# OMSI_TABLE_R12_v3.net
KiCad netlist of a schematic drawn in EAGLE
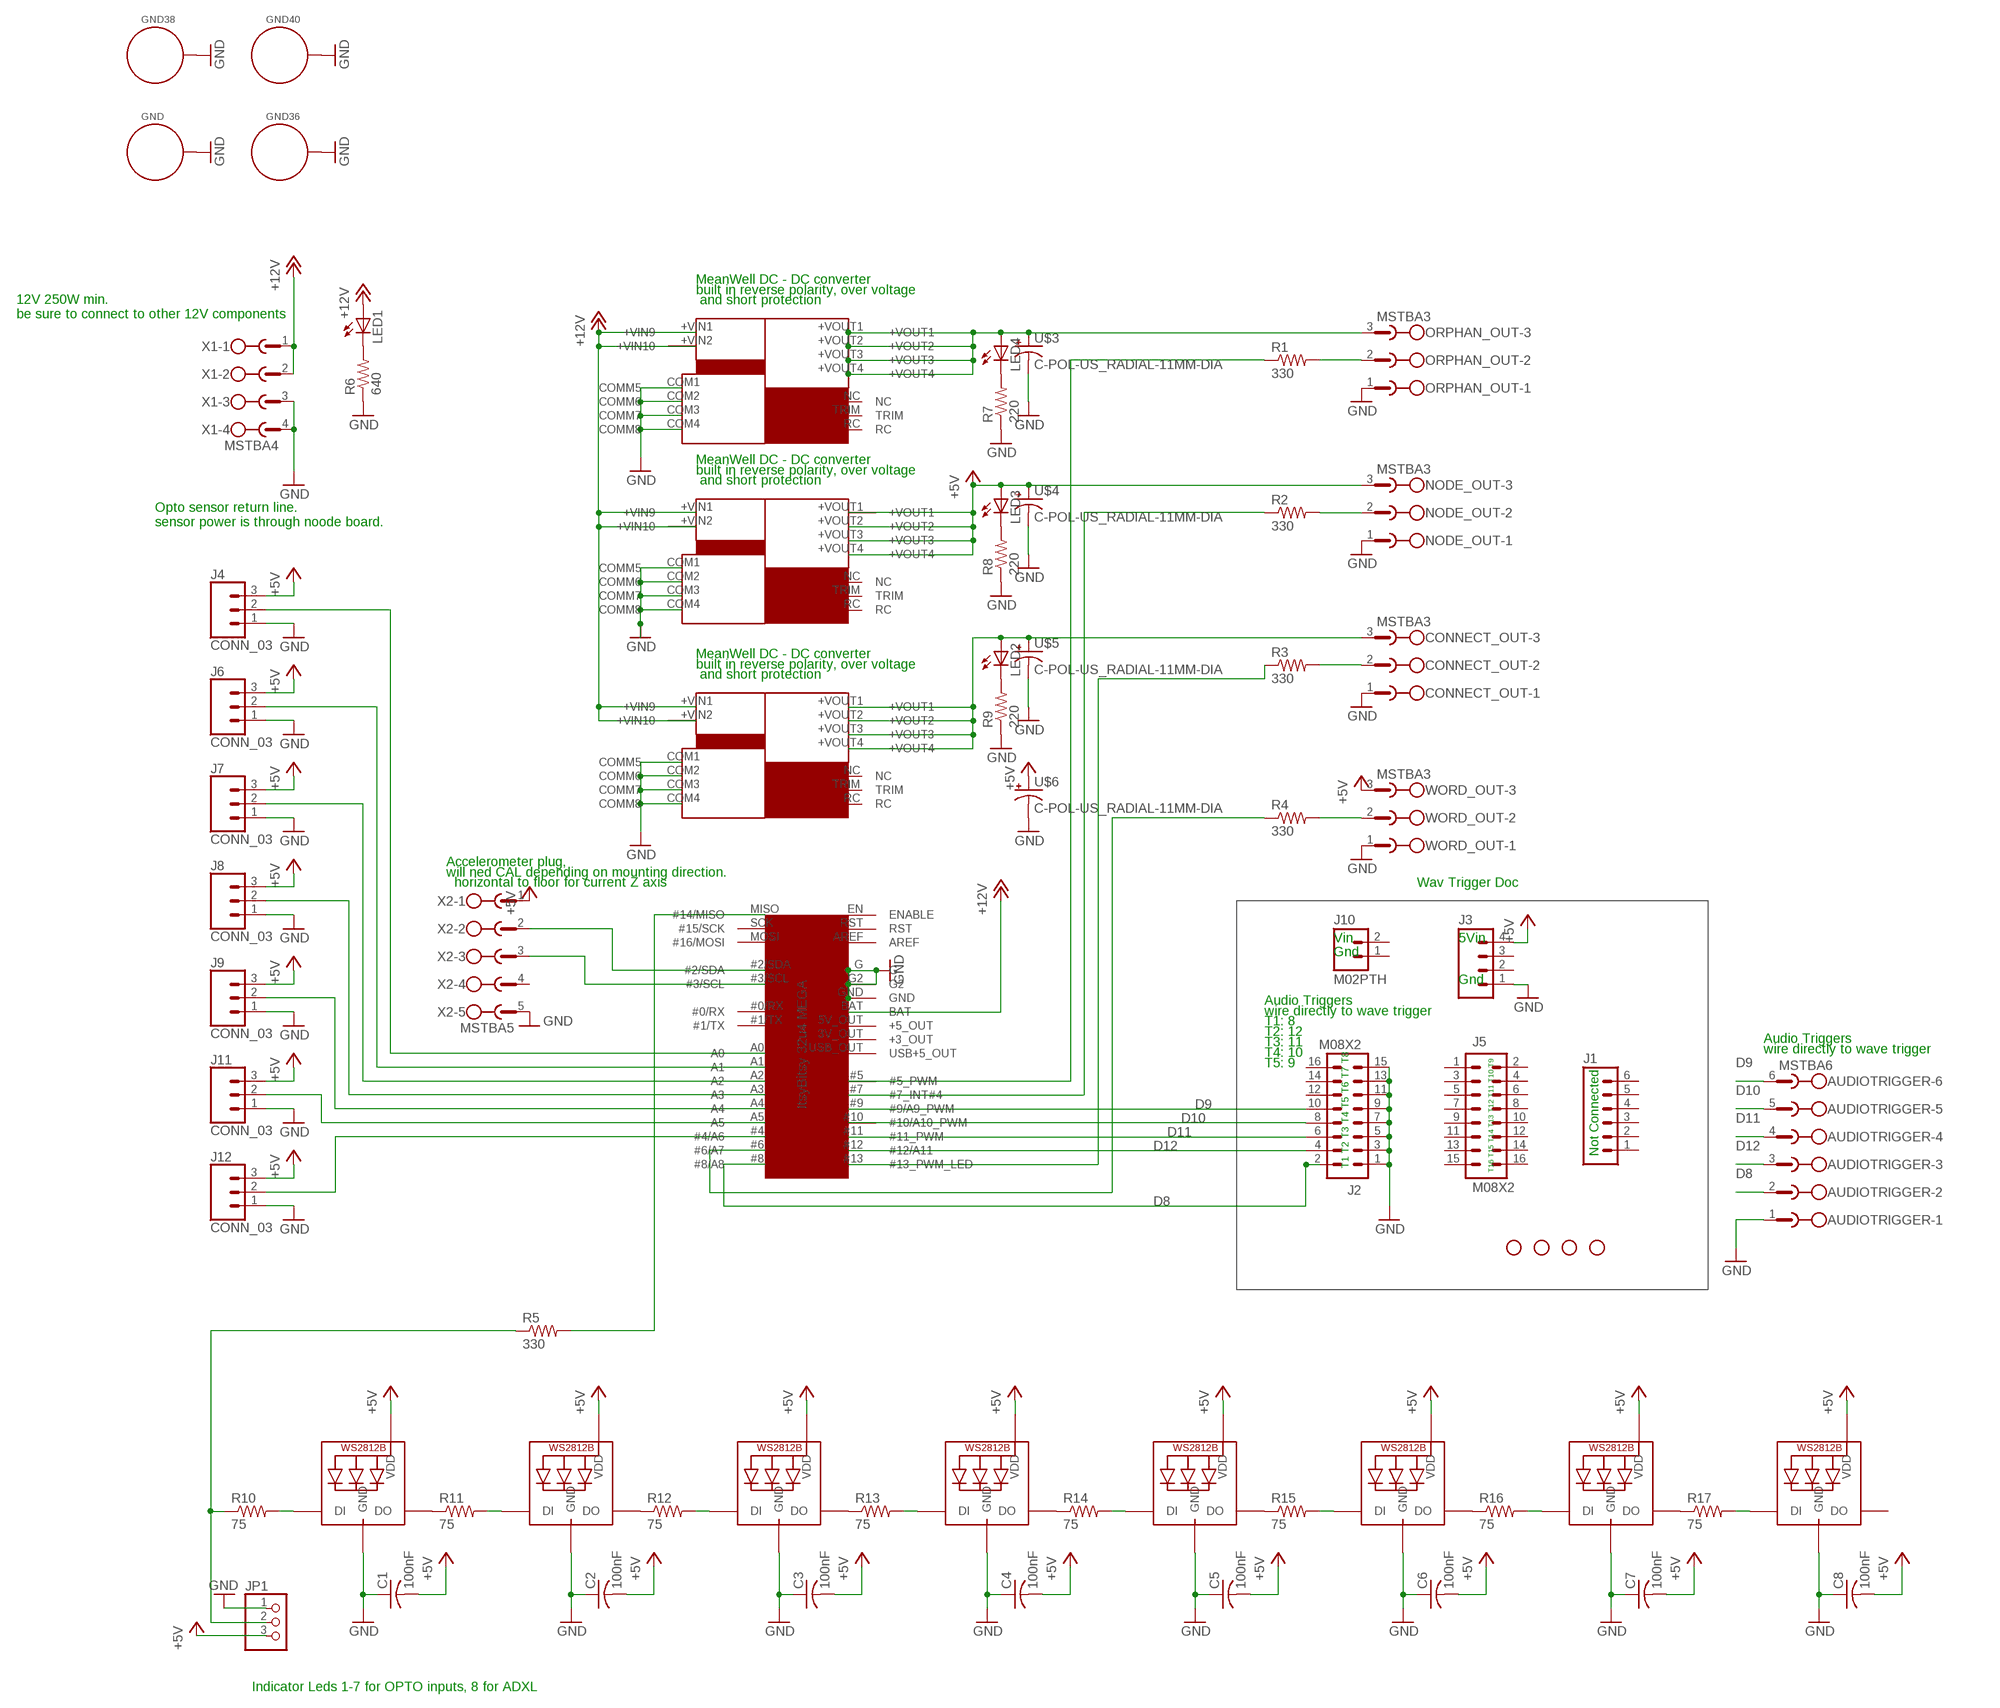
[diagram p0: schematic, sheet 1]

(export (version "E")
  (design (tool "Eeschema 10.0.6"))
  (components
    (comp (ref "AUDIOTRIGGER")
      (value "MSTBA6")
      (footprint "eagle-import:MSTBA6")
      (fields (field (name "MF") "FARNELL") (field (name "MPN") "1757284"))
      (libsource (lib "eagle-import") (part "MSTBA6"))
    )
    (comp (ref "C1")
      (value "100nF")
      (footprint "eagle-import:C0805")
      (libsource (lib "eagle-import") (part "C-USC0805"))
    )
    (comp (ref "C2")
      (value "100nF")
      (footprint "eagle-import:C0805")
      (libsource (lib "eagle-import") (part "C-USC0805"))
    )
    (comp (ref "C3")
      (value "100nF")
      (footprint "eagle-import:C0805")
      (libsource (lib "eagle-import") (part "C-USC0805"))
    )
    (comp (ref "C4")
      (value "100nF")
      (footprint "eagle-import:C0805")
      (libsource (lib "eagle-import") (part "C-USC0805"))
    )
    (comp (ref "C5")
      (value "100nF")
      (footprint "eagle-import:C0805")
      (libsource (lib "eagle-import") (part "C-USC0805"))
    )
    (comp (ref "C6")
      (value "100nF")
      (footprint "eagle-import:C0805")
      (libsource (lib "eagle-import") (part "C-USC0805"))
    )
    (comp (ref "C7")
      (value "100nF")
      (footprint "eagle-import:C0805")
      (libsource (lib "eagle-import") (part "C-USC0805"))
    )
    (comp (ref "C8")
      (value "100nF")
      (footprint "eagle-import:C0805")
      (libsource (lib "eagle-import") (part "C-USC0805"))
    )
    (comp (ref "CONNECT_OUT")
      (value "MSTBA3")
      (footprint "eagle-import:MSTBA3")
      (fields (field (name "MF") "FARNELL") (field (name "MPN") "1757255"))
      (libsource (lib "eagle-import") (part "MSTBA3"))
    )
    (comp (ref "GND")
      (value "STANDOFF_ELECTRICAL5-32")
      (footprint "eagle-import:STANDOFF_ELECTRICAL_5_32")
      (libsource (lib "eagle-import") (part "STANDOFF_ELECTRICAL5-32"))
    )
    (comp (ref "GND36")
      (value "STANDOFF_ELECTRICAL5-32")
      (footprint "eagle-import:STANDOFF_ELECTRICAL_5_32")
      (libsource (lib "eagle-import") (part "STANDOFF_ELECTRICAL5-32"))
    )
    (comp (ref "GND38")
      (value "STANDOFF_ELECTRICAL5-32")
      (footprint "eagle-import:STANDOFF_ELECTRICAL_5_32")
      (libsource (lib "eagle-import") (part "STANDOFF_ELECTRICAL5-32"))
    )
    (comp (ref "GND40")
      (value "STANDOFF_ELECTRICAL5-32")
      (footprint "eagle-import:STANDOFF_ELECTRICAL_5_32")
      (libsource (lib "eagle-import") (part "STANDOFF_ELECTRICAL5-32"))
    )
    (comp (ref "J1")
      (value "M06SIP")
      (footprint "eagle-import:1X06")
      (libsource (lib "eagle-import") (part "M06SIP"))
    )
    (comp (ref "J2")
      (value "M08X2")
      (footprint "eagle-import:2X8")
      (libsource (lib "eagle-import") (part "M08X2"))
    )
    (comp (ref "J3")
      (value "M04PTH")
      (footprint "eagle-import:1X04")
      (libsource (lib "eagle-import") (part "M04PTH"))
    )
    (comp (ref "J4")
      (value "CONN_03")
      (footprint "eagle-import:1X03_3.5MM_RA")
      (libsource (lib "eagle-import") (part "CONN_03"))
    )
    (comp (ref "J5")
      (value "M08X2")
      (footprint "eagle-import:2X8")
      (libsource (lib "eagle-import") (part "M08X2"))
    )
    (comp (ref "J6")
      (value "CONN_03")
      (footprint "eagle-import:1X03_3.5MM_RA")
      (libsource (lib "eagle-import") (part "CONN_03"))
    )
    (comp (ref "J7")
      (value "CONN_03")
      (footprint "eagle-import:1X03_3.5MM_RA")
      (libsource (lib "eagle-import") (part "CONN_03"))
    )
    (comp (ref "J8")
      (value "CONN_03")
      (footprint "eagle-import:1X03_3.5MM_RA")
      (libsource (lib "eagle-import") (part "CONN_03"))
    )
    (comp (ref "J9")
      (value "CONN_03")
      (footprint "eagle-import:1X03_3.5MM_RA")
      (libsource (lib "eagle-import") (part "CONN_03"))
    )
    (comp (ref "J10")
      (value "M02PTH")
      (footprint "eagle-import:1X02")
      (libsource (lib "eagle-import") (part "M02PTH"))
    )
    (comp (ref "J11")
      (value "CONN_03")
      (footprint "eagle-import:1X03_3.5MM_RA")
      (libsource (lib "eagle-import") (part "CONN_03"))
    )
    (comp (ref "J12")
      (value "CONN_03")
      (footprint "eagle-import:1X03_3.5MM_RA")
      (libsource (lib "eagle-import") (part "CONN_03"))
    )
    (comp (ref "JP1")
      (value "PINHD-1X3")
      (footprint "eagle-import:1X03")
      (libsource (lib "eagle-import") (part "PINHD-1X3"))
    )
    (comp (ref "LED1")
      (value "LEDCHIPLED_1206")
      (footprint "eagle-import:CHIPLED_1206")
      (libsource (lib "eagle-import") (part "LEDCHIPLED_1206"))
    )
    (comp (ref "LED2")
      (value "LEDCHIPLED_1206")
      (footprint "eagle-import:CHIPLED_1206")
      (libsource (lib "eagle-import") (part "LEDCHIPLED_1206"))
    )
    (comp (ref "LED3")
      (value "LEDCHIPLED_1206")
      (footprint "eagle-import:CHIPLED_1206")
      (libsource (lib "eagle-import") (part "LEDCHIPLED_1206"))
    )
    (comp (ref "LED4")
      (value "LEDCHIPLED_1206")
      (footprint "eagle-import:CHIPLED_1206")
      (libsource (lib "eagle-import") (part "LEDCHIPLED_1206"))
    )
    (comp (ref "LED5")
      (value "WS2812B")
      (footprint "eagle-import:WS2812D-F5")
      (libsource (lib "eagle-import") (part "WS2812B"))
    )
    (comp (ref "LED6")
      (value "WS2812B")
      (footprint "eagle-import:WS2812D-F5")
      (libsource (lib "eagle-import") (part "WS2812B"))
    )
    (comp (ref "LED7")
      (value "WS2812B")
      (footprint "eagle-import:WS2812D-F5")
      (libsource (lib "eagle-import") (part "WS2812B"))
    )
    (comp (ref "LED8")
      (value "WS2812B")
      (footprint "eagle-import:WS2812D-F5")
      (libsource (lib "eagle-import") (part "WS2812B"))
    )
    (comp (ref "LED9")
      (value "WS2812B")
      (footprint "eagle-import:WS2812D-F5")
      (libsource (lib "eagle-import") (part "WS2812B"))
    )
    (comp (ref "LED10")
      (value "WS2812B")
      (footprint "eagle-import:WS2812D-F5")
      (libsource (lib "eagle-import") (part "WS2812B"))
    )
    (comp (ref "LED11")
      (value "WS2812B")
      (footprint "eagle-import:WS2812D-F5")
      (libsource (lib "eagle-import") (part "WS2812B"))
    )
    (comp (ref "LED12")
      (value "WS2812B")
      (footprint "eagle-import:WS2812D-F5")
      (libsource (lib "eagle-import") (part "WS2812B"))
    )
    (comp (ref "MEANWELL_NID100_1")
      (value "MEANWELL_NID100")
      (footprint "eagle-import:MEANWELL_NID100")
      (libsource (lib "eagle-import") (part "MEANWELL_NID100"))
    )
    (comp (ref "MEANWELL_NID100_2")
      (value "MEANWELL_NID100")
      (footprint "eagle-import:MEANWELL_NID100")
      (libsource (lib "eagle-import") (part "MEANWELL_NID100"))
    )
    (comp (ref "MEANWELL_NID100_3")
      (value "MEANWELL_NID100")
      (footprint "eagle-import:MEANWELL_NID100")
      (libsource (lib "eagle-import") (part "MEANWELL_NID100"))
    )
    (comp (ref "NODE_OUT")
      (value "MSTBA3")
      (footprint "eagle-import:MSTBA3")
      (fields (field (name "MF") "FARNELL") (field (name "MPN") "1757255"))
      (libsource (lib "eagle-import") (part "MSTBA3"))
    )
    (comp (ref "ORPHAN_OUT")
      (value "MSTBA3")
      (footprint "eagle-import:MSTBA3")
      (fields (field (name "MF") "FARNELL") (field (name "MPN") "1757255"))
      (libsource (lib "eagle-import") (part "MSTBA3"))
    )
    (comp (ref "R1")
      (value "330")
      (footprint "eagle-import:RESAD1176W63L850D250B")
      (libsource (lib "eagle-import") (part "R-USAXIAL-11.7MM-PITCH_"))
    )
    (comp (ref "R2")
      (value "330")
      (footprint "eagle-import:RESAD1176W63L850D250B")
      (libsource (lib "eagle-import") (part "R-USAXIAL-11.7MM-PITCH_"))
    )
    (comp (ref "R3")
      (value "330")
      (footprint "eagle-import:RESAD1176W63L850D250B")
      (libsource (lib "eagle-import") (part "R-USAXIAL-11.7MM-PITCH_"))
    )
    (comp (ref "R4")
      (value "330")
      (footprint "eagle-import:RESAD1176W63L850D250B")
      (libsource (lib "eagle-import") (part "R-USAXIAL-11.7MM-PITCH_"))
    )
    (comp (ref "R5")
      (value "330")
      (footprint "eagle-import:RESAD1176W63L850D250B")
      (libsource (lib "eagle-import") (part "R-USAXIAL-11.7MM-PITCH_"))
    )
    (comp (ref "R6")
      (value "640")
      (footprint "eagle-import:R0805")
      (libsource (lib "eagle-import") (part "adafruit_420_R-US_R0805"))
    )
    (comp (ref "R7")
      (value "220")
      (footprint "eagle-import:R0805")
      (libsource (lib "eagle-import") (part "R-US_R0805"))
    )
    (comp (ref "R8")
      (value "220")
      (footprint "eagle-import:R0805")
      (libsource (lib "eagle-import") (part "R-US_R0805"))
    )
    (comp (ref "R9")
      (value "220")
      (footprint "eagle-import:R0805")
      (libsource (lib "eagle-import") (part "R-US_R0805"))
    )
    (comp (ref "R10")
      (value "75")
      (footprint "eagle-import:R0805")
      (libsource (lib "eagle-import") (part "adafruit_420_R-US_R0805"))
    )
    (comp (ref "R11")
      (value "75")
      (footprint "eagle-import:R0805")
      (libsource (lib "eagle-import") (part "adafruit_420_R-US_R0805"))
    )
    (comp (ref "R12")
      (value "75")
      (footprint "eagle-import:R0805")
      (libsource (lib "eagle-import") (part "adafruit_420_R-US_R0805"))
    )
    (comp (ref "R13")
      (value "75")
      (footprint "eagle-import:R0805")
      (libsource (lib "eagle-import") (part "adafruit_420_R-US_R0805"))
    )
    (comp (ref "R14")
      (value "75")
      (footprint "eagle-import:R0805")
      (libsource (lib "eagle-import") (part "adafruit_420_R-US_R0805"))
    )
    (comp (ref "R15")
      (value "75")
      (footprint "eagle-import:R0805")
      (libsource (lib "eagle-import") (part "adafruit_420_R-US_R0805"))
    )
    (comp (ref "R16")
      (value "75")
      (footprint "eagle-import:R0805")
      (libsource (lib "eagle-import") (part "adafruit_420_R-US_R0805"))
    )
    (comp (ref "R17")
      (value "75")
      (footprint "eagle-import:R0805")
      (libsource (lib "eagle-import") (part "adafruit_420_R-US_R0805"))
    )
    (comp (ref "STANDOFF5")
      (value "STAND-OFF")
      (footprint "eagle-import:STAND-OFF")
      (libsource (lib "eagle-import") (part "STAND-OFF"))
    )
    (comp (ref "STANDOFF6")
      (value "STAND-OFF")
      (footprint "eagle-import:STAND-OFF")
      (libsource (lib "eagle-import") (part "STAND-OFF"))
    )
    (comp (ref "STANDOFF7")
      (value "STAND-OFF")
      (footprint "eagle-import:STAND-OFF")
      (libsource (lib "eagle-import") (part "STAND-OFF"))
    )
    (comp (ref "STANDOFF8")
      (value "STAND-OFF")
      (footprint "eagle-import:STAND-OFF")
      (libsource (lib "eagle-import") (part "STAND-OFF"))
    )
    (comp (ref "U$1")
      (value "ITSYBITSY_32U4")
      (footprint "eagle-import:ITSYBITSY_32U4")
      (libsource (lib "eagle-import") (part "ITSYBITSY_32U4"))
    )
    (comp (ref "U$3")
      (value "C-POL-US_RADIAL-11MM-DIA")
      (footprint "eagle-import:CAPPRD508W65D1000H1100B")
      (libsource (lib "eagle-import") (part "C-POL-USRADIAL-11MM-DIA_"))
    )
    (comp (ref "U$4")
      (value "C-POL-US_RADIAL-11MM-DIA")
      (footprint "eagle-import:CAPPRD508W65D1000H1100B")
      (libsource (lib "eagle-import") (part "C-POL-USRADIAL-11MM-DIA_"))
    )
    (comp (ref "U$5")
      (value "C-POL-US_RADIAL-11MM-DIA")
      (footprint "eagle-import:CAPPRD508W65D1000H1100B")
      (libsource (lib "eagle-import") (part "C-POL-USRADIAL-11MM-DIA_"))
    )
    (comp (ref "U$6")
      (value "C-POL-US_RADIAL-11MM-DIA")
      (footprint "eagle-import:CAPPRD508W65D1000H1100B")
      (libsource (lib "eagle-import") (part "C-POL-USRADIAL-11MM-DIA_"))
    )
    (comp (ref "WORD_OUT")
      (value "MSTBA3")
      (footprint "eagle-import:MSTBA3")
      (fields (field (name "MF") "FARNELL") (field (name "MPN") "1757255"))
      (libsource (lib "eagle-import") (part "MSTBA3"))
    )
    (comp (ref "X1")
      (value "MSTBA4")
      (footprint "eagle-import:MSTBA4")
      (fields (field (name "MF") "FARNELL") (field (name "MPN") "1757268"))
      (libsource (lib "eagle-import") (part "MSTBA4"))
    )
    (comp (ref "X2")
      (value "MSTBA5")
      (footprint "eagle-import:MSTBA5")
      (fields (field (name "MPN") "1757271"))
      (libsource (lib "eagle-import") (part "MSTBA5"))
    )
  )
  (nets
    (net (code "1") (name "+5V") (class "Default")
      (node (ref "C1") (pin "2") (pinfunction "2_2") (pintype "passive"))
      (node (ref "C2") (pin "2") (pinfunction "2_2") (pintype "passive"))
      (node (ref "C3") (pin "2") (pinfunction "2_2") (pintype "passive"))
      (node (ref "C4") (pin "2") (pinfunction "2_2") (pintype "passive"))
      (node (ref "C5") (pin "2") (pinfunction "2_2") (pintype "passive"))
      (node (ref "C6") (pin "2") (pinfunction "2_2") (pintype "passive"))
      (node (ref "C7") (pin "2") (pinfunction "2_2") (pintype "passive"))
      (node (ref "C8") (pin "2") (pinfunction "2_2") (pintype "passive"))
      (node (ref "J11") (pin "3") (pinfunction "3_3") (pintype "passive"))
      (node (ref "J12") (pin "3") (pinfunction "3_3") (pintype "passive"))
      (node (ref "J3") (pin "4") (pinfunction "4_4") (pintype "passive"))
      (node (ref "J4") (pin "3") (pinfunction "3_3") (pintype "passive"))
      (node (ref "J6") (pin "3") (pinfunction "3_3") (pintype "passive"))
      (node (ref "J7") (pin "3") (pinfunction "3_3") (pintype "passive"))
      (node (ref "J8") (pin "3") (pinfunction "3_3") (pintype "passive"))
      (node (ref "J9") (pin "3") (pinfunction "3_3") (pintype "passive"))
      (node (ref "JP1") (pin "3") (pinfunction "3_3") (pintype "passive"))
      (node (ref "LED10") (pin "P$2") (pinfunction "VDD_P$2") (pintype "power_in"))
      (node (ref "LED11") (pin "P$2") (pinfunction "VDD_P$2") (pintype "power_in"))
      (node (ref "LED12") (pin "P$2") (pinfunction "VDD_P$2") (pintype "power_in"))
      (node (ref "LED3") (pin "A") (pinfunction "A_A") (pintype "passive"))
      (node (ref "LED5") (pin "P$2") (pinfunction "VDD_P$2") (pintype "power_in"))
      (node (ref "LED6") (pin "P$2") (pinfunction "VDD_P$2") (pintype "power_in"))
      (node (ref "LED7") (pin "P$2") (pinfunction "VDD_P$2") (pintype "power_in"))
      (node (ref "LED8") (pin "P$2") (pinfunction "VDD_P$2") (pintype "power_in"))
      (node (ref "LED9") (pin "P$2") (pinfunction "VDD_P$2") (pintype "power_in"))
      (node (ref "MEANWELL_NID100_3") (pin "+VOUT1") (pinfunction "+VOUT1_+VOUT1") (pintype "power_in"))
      (node (ref "MEANWELL_NID100_3") (pin "+VOUT2") (pinfunction "+VOUT2_+VOUT2") (pintype "power_in"))
      (node (ref "MEANWELL_NID100_3") (pin "+VOUT3") (pinfunction "+VOUT3_+VOUT3") (pintype "power_in"))
      (node (ref "MEANWELL_NID100_3") (pin "+VOUT4") (pinfunction "+VOUT4_+VOUT4") (pintype "power_in"))
      (node (ref "NODE_OUT") (pin "3") (pinfunction "1_3") (pintype "passive"))
      (node (ref "U$4") (pin "1") (pinfunction "+_1") (pintype "passive"))
      (node (ref "U$6") (pin "1") (pinfunction "+_1") (pintype "passive"))
      (node (ref "WORD_OUT") (pin "3") (pinfunction "1_3") (pintype "passive"))
      (node (ref "X2") (pin "1") (pinfunction "1_1") (pintype "passive"))
    )
    (net (code "2") (name "+12V") (class "Default")
      (node (ref "LED1") (pin "A") (pinfunction "A_A") (pintype "passive"))
      (node (ref "MEANWELL_NID100_1") (pin "+VIN1") (pinfunction "+VIN9_+VIN1") (pintype "power_in"))
      (node (ref "MEANWELL_NID100_1") (pin "+VIN2") (pinfunction "+VIN10_+VIN2") (pintype "power_in"))
      (node (ref "MEANWELL_NID100_2") (pin "+VIN1") (pinfunction "+VIN9_+VIN1") (pintype "power_in"))
      (node (ref "MEANWELL_NID100_2") (pin "+VIN2") (pinfunction "+VIN10_+VIN2") (pintype "power_in"))
      (node (ref "MEANWELL_NID100_3") (pin "+VIN1") (pinfunction "+VIN9_+VIN1") (pintype "power_in"))
      (node (ref "MEANWELL_NID100_3") (pin "+VIN2") (pinfunction "+VIN10_+VIN2") (pintype "power_in"))
      (node (ref "U$1") (pin "BAT") (pinfunction "BAT_BAT") (pintype "power_in"))
      (node (ref "X1") (pin "1") (pinfunction "1_1") (pintype "passive"))
      (node (ref "X1") (pin "2") (pinfunction "1_2") (pintype "passive"))
    )
    (net (code "3") (name "/+3_OUT") (class "Default")
      (node (ref "U$1") (pin "3V_OUT") (pinfunction "+3_OUT_3V_OUT") (pintype "power_in"))
    )
    (net (code "4") (name "/+5_OUT") (class "Default")
      (node (ref "U$1") (pin "5V_OUT") (pinfunction "+5_OUT_5V_OUT") (pintype "power_in"))
    )
    (net (code "5") (name "/AREF") (class "Default")
      (node (ref "U$1") (pin "AREF") (pinfunction "AREF_AREF") (pintype "power_in"))
    )
    (net (code "6") (name "/D8") (class "Default")
      (node (ref "AUDIOTRIGGER") (pin "2") (pinfunction "1_2") (pintype "passive"))
      (node (ref "J2") (pin "2") (pinfunction "2_2") (pintype "passive"))
      (node (ref "U$1") (pin "#8") (pinfunction "#8/A8_#8") (pintype "bidirectional"))
    )
    (net (code "7") (name "/D9") (class "Default")
      (node (ref "AUDIOTRIGGER") (pin "6") (pinfunction "1_6") (pintype "passive"))
      (node (ref "J2") (pin "10") (pinfunction "10_10") (pintype "passive"))
      (node (ref "U$1") (pin "#9") (pinfunction "#9/A9_PWM_#9") (pintype "bidirectional"))
    )
    (net (code "8") (name "/D10") (class "Default")
      (node (ref "AUDIOTRIGGER") (pin "5") (pinfunction "1_5") (pintype "passive"))
      (node (ref "J2") (pin "8") (pinfunction "8_8") (pintype "passive"))
      (node (ref "U$1") (pin "#10") (pinfunction "#10/A10_PWM_#10") (pintype "bidirectional"))
    )
    (net (code "9") (name "/D11") (class "Default")
      (node (ref "AUDIOTRIGGER") (pin "4") (pinfunction "1_4") (pintype "passive"))
      (node (ref "J2") (pin "6") (pinfunction "6_6") (pintype "passive"))
      (node (ref "U$1") (pin "#11") (pinfunction "#11_PWM_#11") (pintype "bidirectional"))
    )
    (net (code "10") (name "/D12") (class "Default")
      (node (ref "AUDIOTRIGGER") (pin "3") (pinfunction "1_3") (pintype "passive"))
      (node (ref "J2") (pin "4") (pinfunction "4_4") (pintype "passive"))
      (node (ref "U$1") (pin "#12") (pinfunction "#12/A11_#12") (pintype "bidirectional"))
    )
    (net (code "11") (name "/RST") (class "Default")
      (node (ref "U$1") (pin "RST") (pinfunction "RST_RST") (pintype "power_in"))
    )
    (net (code "12") (name "/USB+5_OUT") (class "Default")
      (node (ref "U$1") (pin "USB_OUT") (pinfunction "USB+5_OUT_USB_OUT") (pintype "power_in"))
    )
    (net (code "13") (name "GND") (class "Default")
      (node (ref "AUDIOTRIGGER") (pin "1") (pinfunction "1_1") (pintype "passive"))
      (node (ref "C1") (pin "1") (pinfunction "1_1") (pintype "passive"))
      (node (ref "C2") (pin "1") (pinfunction "1_1") (pintype "passive"))
      (node (ref "C3") (pin "1") (pinfunction "1_1") (pintype "passive"))
      (node (ref "C4") (pin "1") (pinfunction "1_1") (pintype "passive"))
      (node (ref "C5") (pin "1") (pinfunction "1_1") (pintype "passive"))
      (node (ref "C6") (pin "1") (pinfunction "1_1") (pintype "passive"))
      (node (ref "C7") (pin "1") (pinfunction "1_1") (pintype "passive"))
      (node (ref "C8") (pin "1") (pinfunction "1_1") (pintype "passive"))
      (node (ref "CONNECT_OUT") (pin "1") (pinfunction "1_1") (pintype "passive"))
      (node (ref "GND") (pin "P1") (pinfunction "P$1_P1") (pintype "bidirectional"))
      (node (ref "GND36") (pin "P1") (pinfunction "P$1_P1") (pintype "bidirectional"))
      (node (ref "GND38") (pin "P1") (pinfunction "P$1_P1") (pintype "bidirectional"))
      (node (ref "GND40") (pin "P1") (pinfunction "P$1_P1") (pintype "bidirectional"))
      (node (ref "J11") (pin "1") (pinfunction "1_1") (pintype "passive"))
      (node (ref "J12") (pin "1") (pinfunction "1_1") (pintype "passive"))
      (node (ref "J2") (pin "1") (pinfunction "1_1") (pintype "passive"))
      (node (ref "J2") (pin "11") (pinfunction "11_11") (pintype "passive"))
      (node (ref "J2") (pin "13") (pinfunction "13_13") (pintype "passive"))
      (node (ref "J2") (pin "15") (pinfunction "15_15") (pintype "passive"))
      (node (ref "J2") (pin "3") (pinfunction "3_3") (pintype "passive"))
      (node (ref "J2") (pin "5") (pinfunction "5_5") (pintype "passive"))
      (node (ref "J2") (pin "7") (pinfunction "7_7") (pintype "passive"))
      (node (ref "J2") (pin "9") (pinfunction "9_9") (pintype "passive"))
      (node (ref "J3") (pin "1") (pinfunction "1_1") (pintype "passive"))
      (node (ref "J4") (pin "1") (pinfunction "1_1") (pintype "passive"))
      (node (ref "J6") (pin "1") (pinfunction "1_1") (pintype "passive"))
      (node (ref "J7") (pin "1") (pinfunction "1_1") (pintype "passive"))
      (node (ref "J8") (pin "1") (pinfunction "1_1") (pintype "passive"))
      (node (ref "J9") (pin "1") (pinfunction "1_1") (pintype "passive"))
      (node (ref "JP1") (pin "1") (pinfunction "1_1") (pintype "passive"))
      (node (ref "LED10") (pin "P$3") (pinfunction "GND_P$3") (pintype "power_in"))
      (node (ref "LED11") (pin "P$3") (pinfunction "GND_P$3") (pintype "power_in"))
      (node (ref "LED12") (pin "P$3") (pinfunction "GND_P$3") (pintype "power_in"))
      (node (ref "LED5") (pin "P$3") (pinfunction "GND_P$3") (pintype "power_in"))
      (node (ref "LED6") (pin "P$3") (pinfunction "GND_P$3") (pintype "power_in"))
      (node (ref "LED7") (pin "P$3") (pinfunction "GND_P$3") (pintype "power_in"))
      (node (ref "LED8") (pin "P$3") (pinfunction "GND_P$3") (pintype "power_in"))
      (node (ref "LED9") (pin "P$3") (pinfunction "GND_P$3") (pintype "power_in"))
      (node (ref "MEANWELL_NID100_1") (pin "COM1") (pinfunction "COMM5_COM1") (pintype "power_in"))
      (node (ref "MEANWELL_NID100_1") (pin "COM2") (pinfunction "COMM6_COM2") (pintype "power_in"))
      (node (ref "MEANWELL_NID100_1") (pin "COM3") (pinfunction "COMM7_COM3") (pintype "power_in"))
      (node (ref "MEANWELL_NID100_1") (pin "COM4") (pinfunction "COMM8_COM4") (pintype "power_in"))
      (node (ref "MEANWELL_NID100_2") (pin "COM1") (pinfunction "COMM5_COM1") (pintype "power_in"))
      (node (ref "MEANWELL_NID100_2") (pin "COM2") (pinfunction "COMM6_COM2") (pintype "power_in"))
      (node (ref "MEANWELL_NID100_2") (pin "COM3") (pinfunction "COMM7_COM3") (pintype "power_in"))
      (node (ref "MEANWELL_NID100_2") (pin "COM4") (pinfunction "COMM8_COM4") (pintype "power_in"))
      (node (ref "MEANWELL_NID100_3") (pin "COM1") (pinfunction "COMM5_COM1") (pintype "power_in"))
      (node (ref "MEANWELL_NID100_3") (pin "COM2") (pinfunction "COMM6_COM2") (pintype "power_in"))
      (node (ref "MEANWELL_NID100_3") (pin "COM3") (pinfunction "COMM7_COM3") (pintype "power_in"))
      (node (ref "MEANWELL_NID100_3") (pin "COM4") (pinfunction "COMM8_COM4") (pintype "power_in"))
      (node (ref "NODE_OUT") (pin "1") (pinfunction "1_1") (pintype "passive"))
      (node (ref "ORPHAN_OUT") (pin "1") (pinfunction "1_1") (pintype "passive"))
      (node (ref "R6") (pin "1") (pinfunction "1_1") (pintype "passive"))
      (node (ref "R7") (pin "1") (pinfunction "1_1") (pintype "passive"))
      (node (ref "R8") (pin "1") (pinfunction "1_1") (pintype "passive"))
      (node (ref "R9") (pin "1") (pinfunction "1_1") (pintype "passive"))
      (node (ref "U$1") (pin "G") (pinfunction "G_G") (pintype "power_in"))
      (node (ref "U$1") (pin "G2") (pinfunction "G2_G2") (pintype "power_in"))
      (node (ref "U$1") (pin "GND") (pinfunction "GND_GND") (pintype "power_in"))
      (node (ref "U$3") (pin "2") (pinfunction "-_2") (pintype "passive"))
      (node (ref "U$4") (pin "2") (pinfunction "-_2") (pintype "passive"))
      (node (ref "U$5") (pin "2") (pinfunction "-_2") (pintype "passive"))
      (node (ref "U$6") (pin "2") (pinfunction "-_2") (pintype "passive"))
      (node (ref "WORD_OUT") (pin "1") (pinfunction "1_1") (pintype "passive"))
      (node (ref "X1") (pin "3") (pinfunction "1_3") (pintype "passive"))
      (node (ref "X1") (pin "4") (pinfunction "1_4") (pintype "passive"))
      (node (ref "X2") (pin "5") (pinfunction "1_5") (pintype "passive"))
    )
    (net (code "14") (name "Net-(CONNECT_OUTB-1)") (class "Default")
      (node (ref "CONNECT_OUT") (pin "2") (pinfunction "1_2") (pintype "passive"))
      (node (ref "R3") (pin "2") (pinfunction "2_2") (pintype "passive"))
    )
    (net (code "15") (name "Net-(CONNECT_OUTC-1)") (class "Default")
      (node (ref "CONNECT_OUT") (pin "3") (pinfunction "1_3") (pintype "passive"))
      (node (ref "LED2") (pin "A") (pinfunction "A_A") (pintype "passive"))
      (node (ref "MEANWELL_NID100_1") (pin "+VOUT1") (pinfunction "+VOUT1_+VOUT1") (pintype "power_in"))
      (node (ref "MEANWELL_NID100_1") (pin "+VOUT2") (pinfunction "+VOUT2_+VOUT2") (pintype "power_in"))
      (node (ref "MEANWELL_NID100_1") (pin "+VOUT3") (pinfunction "+VOUT3_+VOUT3") (pintype "power_in"))
      (node (ref "MEANWELL_NID100_1") (pin "+VOUT4") (pinfunction "+VOUT4_+VOUT4") (pintype "power_in"))
      (node (ref "U$5") (pin "1") (pinfunction "+_1") (pintype "passive"))
    )
    (net (code "16") (name "Net-(J4-Pad2)") (class "Default")
      (node (ref "J4") (pin "2") (pinfunction "2_2") (pintype "passive"))
      (node (ref "U$1") (pin "A0") (pinfunction "A0_A0") (pintype "bidirectional"))
    )
    (net (code "17") (name "Net-(J6-Pad2)") (class "Default")
      (node (ref "J6") (pin "2") (pinfunction "2_2") (pintype "passive"))
      (node (ref "U$1") (pin "A1") (pinfunction "A1_A1") (pintype "bidirectional"))
    )
    (net (code "18") (name "Net-(J7-Pad2)") (class "Default")
      (node (ref "J7") (pin "2") (pinfunction "2_2") (pintype "passive"))
      (node (ref "U$1") (pin "A2") (pinfunction "A2_A2") (pintype "bidirectional"))
    )
    (net (code "19") (name "Net-(J8-Pad2)") (class "Default")
      (node (ref "J8") (pin "2") (pinfunction "2_2") (pintype "passive"))
      (node (ref "U$1") (pin "A3") (pinfunction "A3_A3") (pintype "bidirectional"))
    )
    (net (code "20") (name "Net-(J9-Pad2)") (class "Default")
      (node (ref "J9") (pin "2") (pinfunction "2_2") (pintype "passive"))
      (node (ref "U$1") (pin "A4") (pinfunction "A4_A4") (pintype "bidirectional"))
    )
    (net (code "21") (name "Net-(J11-Pad2)") (class "Default")
      (node (ref "J11") (pin "2") (pinfunction "2_2") (pintype "passive"))
      (node (ref "U$1") (pin "A5") (pinfunction "A5_A5") (pintype "bidirectional"))
    )
    (net (code "22") (name "Net-(JP1-Pad2)") (class "Default")
      (node (ref "JP1") (pin "2") (pinfunction "2_2") (pintype "passive"))
      (node (ref "R10") (pin "1") (pinfunction "1_1") (pintype "passive"))
      (node (ref "R5") (pin "1") (pinfunction "1_1") (pintype "passive"))
    )
    (net (code "23") (name "Net-(LED1-PadC)") (class "Default")
      (node (ref "LED1") (pin "C") (pinfunction "C_C") (pintype "passive"))
      (node (ref "R6") (pin "2") (pinfunction "2_2") (pintype "passive"))
    )
    (net (code "24") (name "Net-(LED2-PadC)") (class "Default")
      (node (ref "LED2") (pin "C") (pinfunction "C_C") (pintype "passive"))
      (node (ref "R9") (pin "2") (pinfunction "2_2") (pintype "passive"))
    )
    (net (code "25") (name "Net-(LED3-PadC)") (class "Default")
      (node (ref "LED3") (pin "C") (pinfunction "C_C") (pintype "passive"))
      (node (ref "R8") (pin "2") (pinfunction "2_2") (pintype "passive"))
    )
    (net (code "26") (name "Net-(LED4-PadC)") (class "Default")
      (node (ref "LED4") (pin "C") (pinfunction "C_C") (pintype "passive"))
      (node (ref "R7") (pin "2") (pinfunction "2_2") (pintype "passive"))
    )
    (net (code "27") (name "Net-(LED5-DI)") (class "Default")
      (node (ref "LED5") (pin "P$4") (pinfunction "DI_P$4") (pintype "input"))
      (node (ref "R10") (pin "2") (pinfunction "2_2") (pintype "passive"))
    )
    (net (code "28") (name "Net-(LED5-DO)") (class "Default")
      (node (ref "LED5") (pin "P$1") (pinfunction "DO_P$1") (pintype "output"))
      (node (ref "R11") (pin "1") (pinfunction "1_1") (pintype "passive"))
    )
    (net (code "29") (name "Net-(LED6-DI)") (class "Default")
      (node (ref "LED6") (pin "P$4") (pinfunction "DI_P$4") (pintype "input"))
      (node (ref "R11") (pin "2") (pinfunction "2_2") (pintype "passive"))
    )
    (net (code "30") (name "Net-(LED6-DO)") (class "Default")
      (node (ref "LED6") (pin "P$1") (pinfunction "DO_P$1") (pintype "output"))
      (node (ref "R12") (pin "1") (pinfunction "1_1") (pintype "passive"))
    )
    (net (code "31") (name "Net-(LED7-DI)") (class "Default")
      (node (ref "LED7") (pin "P$4") (pinfunction "DI_P$4") (pintype "input"))
      (node (ref "R12") (pin "2") (pinfunction "2_2") (pintype "passive"))
    )
    (net (code "32") (name "Net-(LED7-DO)") (class "Default")
      (node (ref "LED7") (pin "P$1") (pinfunction "DO_P$1") (pintype "output"))
      (node (ref "R13") (pin "1") (pinfunction "1_1") (pintype "passive"))
    )
    (net (code "33") (name "Net-(LED8-DI)") (class "Default")
      (node (ref "LED8") (pin "P$4") (pinfunction "DI_P$4") (pintype "input"))
      (node (ref "R13") (pin "2") (pinfunction "2_2") (pintype "passive"))
    )
    (net (code "34") (name "Net-(LED8-DO)") (class "Default")
      (node (ref "LED8") (pin "P$1") (pinfunction "DO_P$1") (pintype "output"))
      (node (ref "R14") (pin "1") (pinfunction "1_1") (pintype "passive"))
    )
    (net (code "35") (name "Net-(LED9-DI)") (class "Default")
      (node (ref "LED9") (pin "P$4") (pinfunction "DI_P$4") (pintype "input"))
      (node (ref "R14") (pin "2") (pinfunction "2_2") (pintype "passive"))
    )
    (net (code "36") (name "Net-(LED9-DO)") (class "Default")
      (node (ref "LED9") (pin "P$1") (pinfunction "DO_P$1") (pintype "output"))
      (node (ref "R15") (pin "1") (pinfunction "1_1") (pintype "passive"))
    )
    (net (code "37") (name "Net-(LED10-DI)") (class "Default")
      (node (ref "LED10") (pin "P$4") (pinfunction "DI_P$4") (pintype "input"))
      (node (ref "R15") (pin "2") (pinfunction "2_2") (pintype "passive"))
    )
    (net (code "38") (name "Net-(LED10-DO)") (class "Default")
      (node (ref "LED10") (pin "P$1") (pinfunction "DO_P$1") (pintype "output"))
      (node (ref "R16") (pin "1") (pinfunction "1_1") (pintype "passive"))
    )
    (net (code "39") (name "Net-(LED11-DI)") (class "Default")
      (node (ref "LED11") (pin "P$4") (pinfunction "DI_P$4") (pintype "input"))
      (node (ref "R16") (pin "2") (pinfunction "2_2") (pintype "passive"))
    )
    (net (code "40") (name "Net-(LED11-DO)") (class "Default")
      (node (ref "LED11") (pin "P$1") (pinfunction "DO_P$1") (pintype "output"))
      (node (ref "R17") (pin "1") (pinfunction "1_1") (pintype "passive"))
    )
    (net (code "41") (name "Net-(LED12-DI)") (class "Default")
      (node (ref "LED12") (pin "P$4") (pinfunction "DI_P$4") (pintype "input"))
      (node (ref "R17") (pin "2") (pinfunction "2_2") (pintype "passive"))
    )
    (net (code "42") (name "Net-(NODE_OUTB-1)") (class "Default")
      (node (ref "NODE_OUT") (pin "2") (pinfunction "1_2") (pintype "passive"))
      (node (ref "R2") (pin "2") (pinfunction "2_2") (pintype "passive"))
    )
    (net (code "43") (name "Net-(ORPHAN_OUTB-1)") (class "Default")
      (node (ref "ORPHAN_OUT") (pin "2") (pinfunction "1_2") (pintype "passive"))
      (node (ref "R1") (pin "2") (pinfunction "2_2") (pintype "passive"))
    )
    (net (code "44") (name "Net-(ORPHAN_OUTC-1)") (class "Default")
      (node (ref "LED4") (pin "A") (pinfunction "A_A") (pintype "passive"))
      (node (ref "MEANWELL_NID100_2") (pin "+VOUT1") (pinfunction "+VOUT1_+VOUT1") (pintype "power_in"))
      (node (ref "MEANWELL_NID100_2") (pin "+VOUT2") (pinfunction "+VOUT2_+VOUT2") (pintype "power_in"))
      (node (ref "MEANWELL_NID100_2") (pin "+VOUT3") (pinfunction "+VOUT3_+VOUT3") (pintype "power_in"))
      (node (ref "MEANWELL_NID100_2") (pin "+VOUT4") (pinfunction "+VOUT4_+VOUT4") (pintype "power_in"))
      (node (ref "ORPHAN_OUT") (pin "3") (pinfunction "1_3") (pintype "passive"))
      (node (ref "U$3") (pin "1") (pinfunction "+_1") (pintype "passive"))
    )
    (net (code "45") (name "Net-(U$1-#4{slash}A6)") (class "Default")
      (node (ref "J12") (pin "2") (pinfunction "2_2") (pintype "passive"))
      (node (ref "U$1") (pin "#4") (pinfunction "#4/A6_#4") (pintype "input"))
    )
    (net (code "46") (name "Net-(U$1-#5_PWM)") (class "Default")
      (node (ref "R1") (pin "1") (pinfunction "1_1") (pintype "passive"))
      (node (ref "U$1") (pin "#5") (pinfunction "#5_PWM_#5") (pintype "bidirectional"))
    )
    (net (code "47") (name "Net-(U$1-#6{slash}A7)") (class "Default")
      (node (ref "R4") (pin "1") (pinfunction "1_1") (pintype "passive"))
      (node (ref "U$1") (pin "#6") (pinfunction "#6/A7_#6") (pintype "bidirectional"))
    )
    (net (code "48") (name "Net-(U$1-#7_INT#4)") (class "Default")
      (node (ref "R2") (pin "1") (pinfunction "1_1") (pintype "passive"))
      (node (ref "U$1") (pin "#7") (pinfunction "#7_INT#4_#7") (pintype "bidirectional"))
    )
    (net (code "49") (name "Net-(U$1-#13_PWM_LED)") (class "Default")
      (node (ref "R3") (pin "1") (pinfunction "1_1") (pintype "passive"))
      (node (ref "U$1") (pin "#13") (pinfunction "#13_PWM_LED_#13") (pintype "bidirectional"))
    )
    (net (code "50") (name "Net-(U$1-#14{slash}MISO)") (class "Default")
      (node (ref "R5") (pin "2") (pinfunction "2_2") (pintype "passive"))
      (node (ref "U$1") (pin "MISO") (pinfunction "#14/MISO_MISO") (pintype "bidirectional"))
    )
    (net (code "51") (name "Net-(WORD_OUTB-1)") (class "Default")
      (node (ref "R4") (pin "2") (pinfunction "2_2") (pintype "passive"))
      (node (ref "WORD_OUT") (pin "2") (pinfunction "1_2") (pintype "passive"))
    )
    (net (code "52") (name "Net-(X2B-1)") (class "Default")
      (node (ref "U$1") (pin "#2/SDA") (pinfunction "#2/SDA_#2/SDA") (pintype "bidirectional"))
      (node (ref "X2") (pin "2") (pinfunction "1_2") (pintype "passive"))
    )
    (net (code "53") (name "Net-(X2C-1)") (class "Default")
      (node (ref "U$1") (pin "#3/SCL") (pinfunction "#3/SCL_#3/SCL") (pintype "bidirectional"))
      (node (ref "X2") (pin "3") (pinfunction "1_3") (pintype "passive"))
    )
    (net (code "54") (name "unconnected-(J1-Pad1)") (class "Default")
      (node (ref "J1") (pin "1") (pinfunction "1_1") (pintype "passive"))
    )
    (net (code "55") (name "unconnected-(J1-Pad2)") (class "Default")
      (node (ref "J1") (pin "2") (pinfunction "2_2") (pintype "passive"))
    )
    (net (code "56") (name "unconnected-(J1-Pad3)") (class "Default")
      (node (ref "J1") (pin "3") (pinfunction "3_3") (pintype "passive"))
    )
    (net (code "57") (name "unconnected-(J1-Pad4)") (class "Default")
      (node (ref "J1") (pin "4") (pinfunction "4_4") (pintype "passive"))
    )
    (net (code "58") (name "unconnected-(J1-Pad5)") (class "Default")
      (node (ref "J1") (pin "5") (pinfunction "5_5") (pintype "passive"))
    )
    (net (code "59") (name "unconnected-(J1-Pad6)") (class "Default")
      (node (ref "J1") (pin "6") (pinfunction "6_6") (pintype "passive"))
    )
    (net (code "60") (name "unconnected-(J2-Pad12)") (class "Default")
      (node (ref "J2") (pin "12") (pinfunction "12_12") (pintype "passive"))
    )
    (net (code "61") (name "unconnected-(J2-Pad14)") (class "Default")
      (node (ref "J2") (pin "14") (pinfunction "14_14") (pintype "passive"))
    )
    (net (code "62") (name "unconnected-(J2-Pad16)") (class "Default")
      (node (ref "J2") (pin "16") (pinfunction "16_16") (pintype "passive"))
    )
    (net (code "63") (name "unconnected-(J3-Pad2)") (class "Default")
      (node (ref "J3") (pin "2") (pinfunction "2_2") (pintype "passive"))
    )
    (net (code "64") (name "unconnected-(J3-Pad3)") (class "Default")
      (node (ref "J3") (pin "3") (pinfunction "3_3") (pintype "passive"))
    )
    (net (code "65") (name "unconnected-(J5-Pad1)") (class "Default")
      (node (ref "J5") (pin "1") (pinfunction "1_1") (pintype "passive"))
    )
    (net (code "66") (name "unconnected-(J5-Pad2)") (class "Default")
      (node (ref "J5") (pin "2") (pinfunction "2_2") (pintype "passive"))
    )
    (net (code "67") (name "unconnected-(J5-Pad3)") (class "Default")
      (node (ref "J5") (pin "3") (pinfunction "3_3") (pintype "passive"))
    )
    (net (code "68") (name "unconnected-(J5-Pad4)") (class "Default")
      (node (ref "J5") (pin "4") (pinfunction "4_4") (pintype "passive"))
    )
    (net (code "69") (name "unconnected-(J5-Pad5)") (class "Default")
      (node (ref "J5") (pin "5") (pinfunction "5_5") (pintype "passive"))
    )
    (net (code "70") (name "unconnected-(J5-Pad6)") (class "Default")
      (node (ref "J5") (pin "6") (pinfunction "6_6") (pintype "passive"))
    )
    (net (code "71") (name "unconnected-(J5-Pad7)") (class "Default")
      (node (ref "J5") (pin "7") (pinfunction "7_7") (pintype "passive"))
    )
    (net (code "72") (name "unconnected-(J5-Pad8)") (class "Default")
      (node (ref "J5") (pin "8") (pinfunction "8_8") (pintype "passive"))
    )
    (net (code "73") (name "unconnected-(J5-Pad9)") (class "Default")
      (node (ref "J5") (pin "9") (pinfunction "9_9") (pintype "passive"))
    )
    (net (code "74") (name "unconnected-(J5-Pad10)") (class "Default")
      (node (ref "J5") (pin "10") (pinfunction "10_10") (pintype "passive"))
    )
    (net (code "75") (name "unconnected-(J5-Pad11)") (class "Default")
      (node (ref "J5") (pin "11") (pinfunction "11_11") (pintype "passive"))
    )
    (net (code "76") (name "unconnected-(J5-Pad12)") (class "Default")
      (node (ref "J5") (pin "12") (pinfunction "12_12") (pintype "passive"))
    )
    (net (code "77") (name "unconnected-(J5-Pad13)") (class "Default")
      (node (ref "J5") (pin "13") (pinfunction "13_13") (pintype "passive"))
    )
    (net (code "78") (name "unconnected-(J5-Pad14)") (class "Default")
      (node (ref "J5") (pin "14") (pinfunction "14_14") (pintype "passive"))
    )
    (net (code "79") (name "unconnected-(J5-Pad15)") (class "Default")
      (node (ref "J5") (pin "15") (pinfunction "15_15") (pintype "passive"))
    )
    (net (code "80") (name "unconnected-(J5-Pad16)") (class "Default")
      (node (ref "J5") (pin "16") (pinfunction "16_16") (pintype "passive"))
    )
    (net (code "81") (name "unconnected-(J10-Pad1)") (class "Default")
      (node (ref "J10") (pin "1") (pinfunction "1_1") (pintype "passive"))
    )
    (net (code "82") (name "unconnected-(J10-Pad2)") (class "Default")
      (node (ref "J10") (pin "2") (pinfunction "2_2") (pintype "passive"))
    )
    (net (code "83") (name "unconnected-(LED12-DO-PadP$1)") (class "Default")
      (node (ref "LED12") (pin "P$1") (pinfunction "DO_P$1") (pintype "output"))
    )
    (net (code "84") (name "unconnected-(MEANWELL_NID100_1-PadNC)") (class "Default")
      (node (ref "MEANWELL_NID100_1") (pin "NC") (pinfunction "NC_NC") (pintype "no_connect"))
    )
    (net (code "85") (name "unconnected-(MEANWELL_NID100_1-PadRC)") (class "Default")
      (node (ref "MEANWELL_NID100_1") (pin "RC") (pinfunction "RC_RC") (pintype "no_connect"))
    )
    (net (code "86") (name "unconnected-(MEANWELL_NID100_1-PadTRIM)") (class "Default")
      (node (ref "MEANWELL_NID100_1") (pin "TRIM") (pinfunction "TRIM_TRIM") (pintype "no_connect"))
    )
    (net (code "87") (name "unconnected-(MEANWELL_NID100_2-PadNC)") (class "Default")
      (node (ref "MEANWELL_NID100_2") (pin "NC") (pinfunction "NC_NC") (pintype "no_connect"))
    )
    (net (code "88") (name "unconnected-(MEANWELL_NID100_2-PadRC)") (class "Default")
      (node (ref "MEANWELL_NID100_2") (pin "RC") (pinfunction "RC_RC") (pintype "no_connect"))
    )
    (net (code "89") (name "unconnected-(MEANWELL_NID100_2-PadTRIM)") (class "Default")
      (node (ref "MEANWELL_NID100_2") (pin "TRIM") (pinfunction "TRIM_TRIM") (pintype "no_connect"))
    )
    (net (code "90") (name "unconnected-(MEANWELL_NID100_3-PadNC)") (class "Default")
      (node (ref "MEANWELL_NID100_3") (pin "NC") (pinfunction "NC_NC") (pintype "no_connect"))
    )
    (net (code "91") (name "unconnected-(MEANWELL_NID100_3-PadRC)") (class "Default")
      (node (ref "MEANWELL_NID100_3") (pin "RC") (pinfunction "RC_RC") (pintype "no_connect"))
    )
    (net (code "92") (name "unconnected-(MEANWELL_NID100_3-PadTRIM)") (class "Default")
      (node (ref "MEANWELL_NID100_3") (pin "TRIM") (pinfunction "TRIM_TRIM") (pintype "no_connect"))
    )
    (net (code "93") (name "unconnected-(U$1-#15{slash}SCK-PadSCK)") (class "Default")
      (node (ref "U$1") (pin "SCK") (pinfunction "#15/SCK_SCK") (pintype "bidirectional"))
    )
    (net (code "94") (name "unconnected-(U$1-#16{slash}MOSI-PadMOSI)") (class "Default")
      (node (ref "U$1") (pin "MOSI") (pinfunction "#16/MOSI_MOSI") (pintype "bidirectional"))
    )
    (net (code "95") (name "unconnected-(U$1-ENABLE-PadEN)") (class "Default")
      (node (ref "U$1") (pin "EN") (pinfunction "ENABLE_EN") (pintype "input"))
    )
    (net (code "96") (name "unconnected-(U$1-Pad#0{slash}RX)") (class "Default")
      (node (ref "U$1") (pin "#0/RX") (pinfunction "#0/RX_#0/RX") (pintype "bidirectional"))
    )
    (net (code "97") (name "unconnected-(U$1-Pad#1{slash}TX)") (class "Default")
      (node (ref "U$1") (pin "#1/TX") (pinfunction "#1/TX_#1/TX") (pintype "bidirectional"))
    )
    (net (code "98") (name "unconnected-(X2D-1-Pad4)") (class "Default")
      (node (ref "X2") (pin "4") (pinfunction "1_4") (pintype "passive"))
    )
  )
)
